# Power.net
KiCad netlist of a schematic drawn in Altium Designer
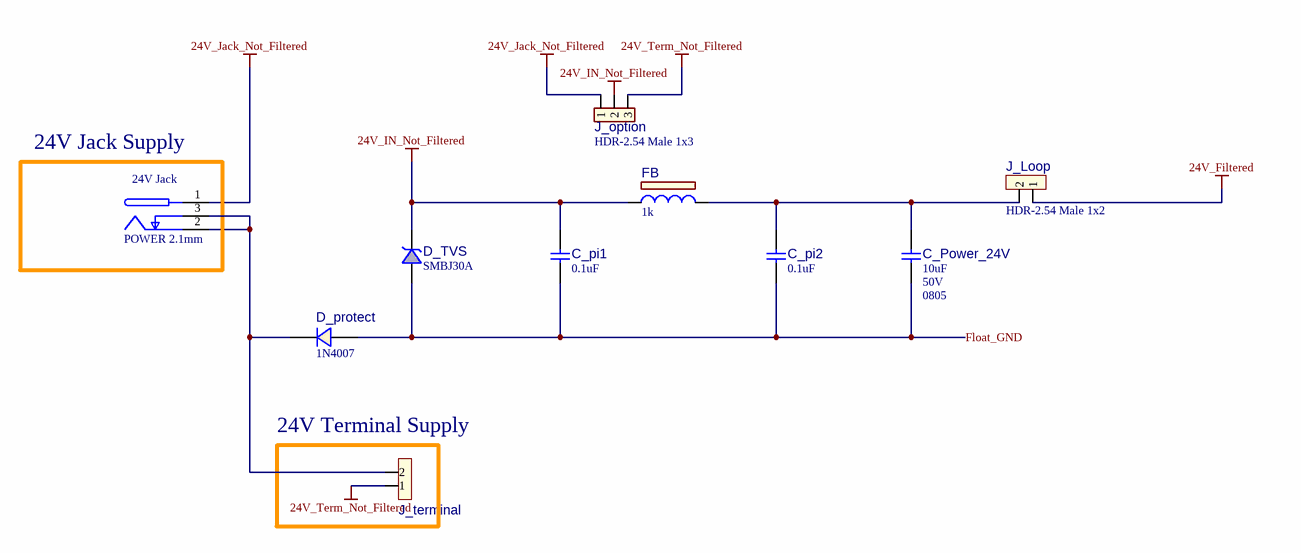
[diagram p0: Power.SchDoc]

(export (version "E")
  (design (tool "Eeschema 10.0.6"))
  (components
    (comp (ref "24V Jack")
      (value "POWER 2.1mm")
      (footprint "CON_JACK_POWER_TH_RA_WE_694106301002")
      (fields
        (field (name "VOLTAGE") "24V")
        (field (name "Comment") "CON JACK 2C 3P SPST")
        (field (name "OWNER") "Narasimha Murthy")
      )
      (libsource (lib "MCL-Offline") (part "CON JACK 2C 3P SPST"))
    )
    (comp (ref "C_pi1")
      (value "0.1uF")
      (footprint "CAP_C_0603")
      (fields
        (field (name "VOLTAGE") "50V")
        (field (name "TOLERANCE") "20%")
        (field (name "Comment") "Capacitor NP")
        (field (name "OWNER") "Leah Whitaker")
      )
      (libsource (lib "MCL-Offline") (part "Capacitor NP"))
    )
    (comp (ref "C_pi2")
      (value "0.1uF")
      (footprint "CAP_C_0603")
      (fields
        (field (name "VOLTAGE") "50V")
        (field (name "TOLERANCE") "20%")
        (field (name "Comment") "Capacitor NP")
        (field (name "OWNER") "Leah Whitaker")
      )
      (libsource (lib "MCL-Offline") (part "Capacitor NP"))
    )
    (comp (ref "C_Power_24V")
      (value "10uF")
      (footprint "CAP_C_0805")
      (fields
        (field (name "VOLTAGE") "50V")
        (field (name "PACKAGE") "0805")
        (field (name "TOLERANCE") "10%")
        (field (name "Comment") "Capacitor NP")
        (field (name "OWNER") "Sam Charles")
      )
      (libsource (lib "MCL-Offline") (part "Capacitor NP"))
    )
    (comp (ref "D_protect")
      (value "1N4007")
      (footprint "DO-41")
      (fields (field (name "Comment") "Diode Single"))
      (libsource (lib "MCL-Offline") (part "Diode Single"))
    )
    (comp (ref "D_TVS")
      (value "SMBJ30A")
      (footprint "DO-214AA_SMB")
      (fields
        (field (name "POWER") "600W")
        (field (name "Comment") "Diode TVS Unidirectional")
        (field (name "OWNER") "Mark Loper")
      )
      (libsource (lib "MCL-Offline") (part "Diode TVS Unidirectional"))
    )
    (comp (ref "FB")
      (value "1k")
      (footprint "IND_C_0603")
      (fields (field (name "Comment") "Ferrite Bead") (field (name "OWNER") "Jojie Batislaon"))
      (libsource (lib "MCL-Offline") (part "Ferrite Bead"))
    )
    (comp (ref "J_Loop")
      (value "HDR-2.54 Male 1x2")
      (footprint "HDR_M_2.54_1x2")
      (fields
        (field (name "VOLTAGE") "250V")
        (field (name "Comment") "Header 1x2")
        (field (name "OWNER") "Narasimha Murthy")
      )
      (libsource (lib "MCL-Offline") (part "Header 1x2"))
    )
    (comp (ref "J_option")
      (value "HDR-2.54 Male 1x3")
      (footprint "HDR_M_2.54_1x3")
      (fields (field (name "OWNER") "Bogdan P (M91398)"))
      (libsource (lib "MCL-Offline") (part "Header 1x3"))
    )
    (comp (ref "J_terminal")
      (value "~")
      (footprint "CON_TERMINAL_3.81_1x2_TH_RA_PHO_1727010")
      (fields (field (name "VOLTAGE") "300V") (field (name "OWNER") "Kamatchi Sundaresan"))
      (libsource (lib "") (part "Header 1x2_1"))
    )
  )
  (nets
    (net (code "1") (name "/Float_GND") (class "Default")
      (node (ref "C_Power_24V") (pin "1") (pinfunction "1_1") (pintype "passive"))
      (node (ref "C_pi1") (pin "1") (pinfunction "1_1") (pintype "passive"))
      (node (ref "C_pi2") (pin "1") (pinfunction "1_1") (pintype "passive"))
      (node (ref "D_TVS") (pin "1") (pinfunction "1_1") (pintype "passive"))
      (node (ref "D_protect") (pin "1") (pinfunction "A_1") (pintype "passive"))
    )
    (net (code "2") (name "24V_Filtered") (class "Default")
      (node (ref "J_Loop") (pin "1") (pinfunction "1_1") (pintype "passive"))
    )
    (net (code "3") (name "24V_IN_Not_Filtered") (class "Default")
      (node (ref "C_pi1") (pin "2") (pinfunction "2_2") (pintype "passive"))
      (node (ref "D_TVS") (pin "2") (pinfunction "2_2") (pintype "passive"))
      (node (ref "FB") (pin "1") (pinfunction "1_1") (pintype "passive"))
      (node (ref "J_option") (pin "2") (pinfunction "2_2") (pintype "passive"))
    )
    (net (code "4") (name "24V_Jack_Not_Filtered") (class "Default")
      (node (ref "24V Jack") (pin "1") (pinfunction "PLUS_1") (pintype "passive"))
      (node (ref "J_option") (pin "1") (pinfunction "1_1") (pintype "passive"))
    )
    (net (code "5") (name "24V_Term_Not_Filtered") (class "Default")
      (node (ref "J_option") (pin "3") (pinfunction "3_3") (pintype "passive"))
      (node (ref "J_terminal") (pin "1") (pinfunction "1_1") (pintype "passive"))
    )
    (net (code "6") (name "Net-(24V Jack-COM)") (class "Default")
      (node (ref "24V Jack") (pin "2") (pinfunction "COM_2") (pintype "passive"))
      (node (ref "24V Jack") (pin "3") (pinfunction "SWITCH_3") (pintype "passive"))
      (node (ref "D_protect") (pin "2") (pinfunction "K_2") (pintype "passive"))
      (node (ref "J_terminal") (pin "2") (pinfunction "2_2") (pintype "passive"))
    )
    (net (code "7") (name "Net-(C_Power_24V-Pad2)") (class "Default")
      (node (ref "C_Power_24V") (pin "2") (pinfunction "2_2") (pintype "passive"))
      (node (ref "C_pi2") (pin "2") (pinfunction "2_2") (pintype "passive"))
      (node (ref "FB") (pin "2") (pinfunction "2_2") (pintype "passive"))
      (node (ref "J_Loop") (pin "2") (pinfunction "2_2") (pintype "passive"))
    )
  )
)
